# Rail_1.net
KiCad netlist of a schematic drawn in Altium Designer
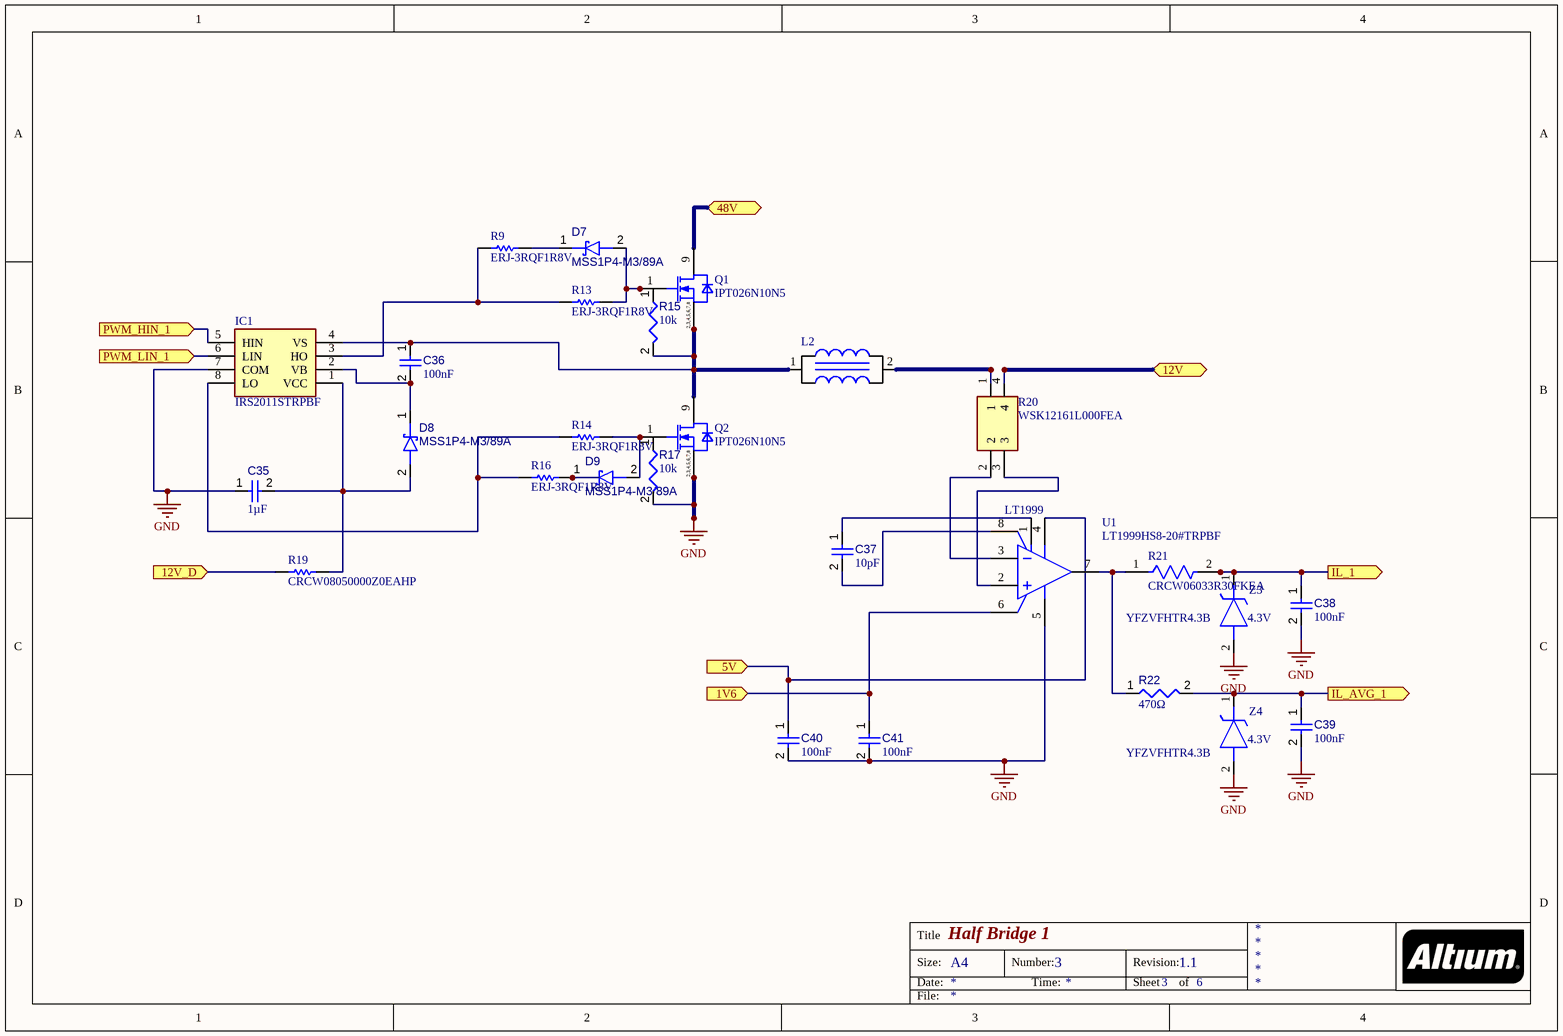
[diagram p0: Rail_1.SchDoc]

(export (version "E")
  (design (tool "Eeschema 10.0.6"))
  (components
    (comp (ref "C35")
      (value "1µF")
      (footprint "CAPC0603(1608)100_L")
      (description "Chip Capacitor, 1µF +/-0.1%, 25V, 0603, Thickness 1 mm")
      (fields (field (name "TOLERANCE") "20%") (field (name "Comment") "Capacitor 1µF +/-0.1% 25V 0603"))
      (libsource (lib "University of Paderborn") (part "CAP-NP-2"))
    )
    (comp (ref "C36")
      (value "100nF")
      (footprint "CAPC1608X90X40ML10T20")
      (description "Chip Capacitor, 100 nF, +/- 10%, 50 V, 0603 (1608 Metric)")
      (fields (field (name "TOLERANCE") "10%") (field (name "Comment") "Capacitor 100 nF +/-10% 50 V 0603"))
      (libsource (lib "University of Paderborn") (part "CAP-NP-2"))
    )
    (comp (ref "C37")
      (value "10pF")
      (footprint "CAPC1608X87X35ML15T15")
      (description "Chip Capacitor, 10 pF, +/- 0.25 pF, 50 V, 0603 (1608 Metric)")
      (fields
        (field (name "TOLERANCE") "0.25%")
        (field (name "Comment") "Capacitor 10 pF +/- 0.25 pF 50 V 0603")
      )
      (libsource (lib "University of Paderborn") (part "CAP-NP-2"))
    )
    (comp (ref "C38")
      (value "100nF")
      (footprint "CAPC1608X90X40ML10T20")
      (description "Chip Capacitor, 100 nF, +/- 10%, 50 V, 0603 (1608 Metric)")
      (fields (field (name "TOLERANCE") "10%") (field (name "Comment") "Capacitor 100 nF +/-10% 50 V 0603"))
      (libsource (lib "University of Paderborn") (part "CAP-NP-2"))
    )
    (comp (ref "C39")
      (value "100nF")
      (footprint "CAPC1608X90X40ML10T20")
      (description "Chip Capacitor, 100 nF, +/- 10%, 50 V, 0603 (1608 Metric)")
      (fields (field (name "TOLERANCE") "10%") (field (name "Comment") "Capacitor 100 nF +/-10% 50 V 0603"))
      (libsource (lib "University of Paderborn") (part "CAP-NP-2"))
    )
    (comp (ref "C40")
      (value "100nF")
      (footprint "CAPC1608X90X40ML10T20")
      (description "Chip Capacitor, 100 nF, +/- 10%, 50 V, 0603 (1608 Metric)")
      (fields (field (name "TOLERANCE") "10%") (field (name "Comment") "Capacitor 100 nF +/-10% 50 V 0603"))
      (libsource (lib "University of Paderborn") (part "CAP-NP-2"))
    )
    (comp (ref "C41")
      (value "100nF")
      (footprint "CAPC1608X90X40ML10T20")
      (description "Chip Capacitor, 100 nF, +/- 10%, 50 V, 0603 (1608 Metric)")
      (fields (field (name "TOLERANCE") "10%") (field (name "Comment") "Capacitor 100 nF +/-10% 50 V 0603"))
      (libsource (lib "University of Paderborn") (part "CAP-NP-2"))
    )
    (comp (ref "D7")
      (value "MSS1P4-M3/89A")
      (footprint "MicroSMP (DO-219AD)")
      (description "Schottky Diodes & Rectifiers 1.0 Amp 40 Volt")
      (libsource (lib "University of Paderborn") (part "D-SKY-KA2"))
    )
    (comp (ref "D8")
      (value "MSS1P4-M3/89A")
      (footprint "MicroSMP (DO-219AD)")
      (description "Schottky Diodes & Rectifiers 1.0 Amp 40 Volt")
      (libsource (lib "University of Paderborn") (part "D-SKY-KA2"))
    )
    (comp (ref "D9")
      (value "MSS1P4-M3/89A")
      (footprint "MicroSMP (DO-219AD)")
      (description "Schottky Diodes & Rectifiers 1.0 Amp 40 Volt")
      (libsource (lib "University of Paderborn") (part "D-SKY-KA2"))
    )
    (comp (ref "IC1")
      (value "IRS2011STRPBF")
      (footprint "SOIC127P600X175-8N-12-V")
      (description "Integrated Circuit")
      (fields (field (name "MOUSER PART NUMBER") "942-IRS2011STRPBF"))
      (libsource (lib "*") (part "IRS2011STRPBF"))
    )
    (comp (ref "L2")
      (value "Inductor (Ansys)")
      (footprint "Inductor-Footprint-1")
      (description "Ansys 3D Model")
      (libsource (lib "University of Paderborn") (part "Inductor"))
    )
    (comp (ref "Q1")
      (value "IPT026N10N5")
      (footprint "INF-PG-HSOF-8-1-0-V")
      (fields (field (name "MANUFACTURER") "Infineon Technologies"))
      (libsource (lib "IPT026N10N5") (part "IPT026N10N5"))
    )
    (comp (ref "Q2")
      (value "IPT026N10N5")
      (footprint "INF-PG-HSOF-8-1-0-V")
      (fields (field (name "MANUFACTURER") "Infineon Technologies"))
      (libsource (lib "IPT026N10N5") (part "IPT026N10N5"))
    )
    (comp (ref "R9")
      (value "ERJ-3RQF1R8V")
      (footprint "RESC1608X55X30LL15T15")
      (fields (field (name "MANUFACTURER") "Panasonic"))
      (libsource (lib "Altium Content Vault") (part "RES"))
    )
    (comp (ref "R13")
      (value "ERJ-3RQF1R8V")
      (footprint "RESC1608X55X30LL15T15")
      (fields (field (name "MANUFACTURER") "Panasonic"))
      (libsource (lib "Altium Content Vault") (part "RES"))
    )
    (comp (ref "R14")
      (value "ERJ-3RQF1R8V")
      (footprint "RESC1608X55X30LL15T15")
      (fields (field (name "MANUFACTURER") "Panasonic"))
      (libsource (lib "Altium Content Vault") (part "RES"))
    )
    (comp (ref "R15")
      (value "10k")
      (footprint "RESC1608X55X25ML10T15")
      (description "Chip Resistor, 10 KOhm, +/- 1%, 01 W, -55 to 155 degC, 0603 (1608 Metric)")
      (fields (field (name "TOLERANCE") "1%") (field (name "POWER") "100mW"))
      (libsource (lib "University of Paderborn") (part "RES-2"))
    )
    (comp (ref "R16")
      (value "ERJ-3RQF1R8V")
      (footprint "RESC1608X55X30LL15T15")
      (fields (field (name "MANUFACTURER") "Panasonic"))
      (libsource (lib "Altium Content Vault") (part "RES"))
    )
    (comp (ref "R17")
      (value "10k")
      (footprint "RESC1608X55X25ML10T15")
      (description "Chip Resistor, 10 KOhm, +/- 1%, 01 W, -55 to 155 degC, 0603 (1608 Metric)")
      (fields (field (name "TOLERANCE") "1%") (field (name "POWER") "100mW"))
      (libsource (lib "University of Paderborn") (part "RES-2"))
    )
    (comp (ref "R19")
      (value "CRCW08050000Z0EAHP")
      (footprint "RESC2013X50X30ML20T20")
      (fields (field (name "MANUFACTURER") "Vishay Dale"))
      (libsource (lib "Altium Content Vault") (part "RES"))
    )
    (comp (ref "R20")
      (value "WSK12161L000FEA")
      (footprint "SamacSys:WSK12161L000FEA")
      (description "Resistor")
      (fields (field (name "MOUSER PART NUMBER") "71-WSK12161L000FEA"))
      (libsource (lib "*") (part "WSK12161L000FEA"))
    )
    (comp (ref "R21")
      (value "CRCW06033R30FKEA")
      (footprint "FP-CRCW0603-e3-IPC_C")
      (description "RES Thick Film, 3.3Ω, 1%, 0.1W, 100ppm/°C, 0603")
      (fields (field (name "TOLERANCE") "1%"))
      (libsource (lib "Altium Content Vault") (part "1029c3af85768c4190bb7ad29bc67b5"))
    )
    (comp (ref "R22")
      (value "470Ω")
      (footprint "RESC0805(2012)_L")
      (description "470R 0.125W 5% 0805 (2012 Metric)  SMD")
      (fields (field (name "POWER") "0.125W") (field (name "TOLERANCE") "5%"))
      (libsource (lib "University of Paderborn") (part "470R5J"))
    )
    (comp (ref "U1")
      (value "LT1999HS8-20#TRPBF")
      (footprint "LT-S8-8_L")
      (fields
        (field (name "LINEAR TECHNOLOGY PART NUMBER") "LT1999-20")
        (field (name "MANUFACTURER") "Linear Technology")
      )
      (libsource (lib "Altium Content Vault") (part "LT-LT1999-8"))
    )
    (comp (ref "Z3")
      (value "YFZVFHTR4.3B")
      (footprint "SamacSys:YFZVFHTR43B")
      (description "Zener Diode")
      (fields (field (name "MOUSER PART NUMBER") "755-YFZVFHTR4.3B"))
      (libsource (lib "*") (part "YFZVFHTR4.3B"))
    )
    (comp (ref "Z4")
      (value "YFZVFHTR4.3B")
      (footprint "SamacSys:YFZVFHTR43B")
      (description "Zener Diode")
      (fields (field (name "MOUSER PART NUMBER") "755-YFZVFHTR4.3B"))
      (libsource (lib "*") (part "YFZVFHTR4.3B"))
    )
  )
  (nets
    (net (code "1") (name "/1V6") (class "Default")
      (node (ref "C41") (pin "1") (pinfunction "1_1") (pintype "passive"))
      (node (ref "U1") (pin "6") (pinfunction "REF_6") (pintype "passive"))
    )
    (net (code "2") (name "/5V") (class "Default")
      (node (ref "C40") (pin "1") (pinfunction "1_1") (pintype "passive"))
      (node (ref "U1") (pin "4") (pinfunction "V+_4") (pintype "passive"))
    )
    (net (code "3") (name "/12V") (class "Default")
      (node (ref "R20") (pin "4") (pinfunction "4_4") (pintype "passive"))
    )
    (net (code "4") (name "/12V_D") (class "Default")
      (node (ref "R19") (pin "1") (pinfunction "1_1") (pintype "passive"))
    )
    (net (code "5") (name "/48V") (class "Default")
      (node (ref "Q1") (pin "9") (pinfunction "DRAIN_9") (pintype "passive"))
    )
    (net (code "6") (name "/IL_1") (class "Default")
      (node (ref "C38") (pin "1") (pinfunction "1_1") (pintype "passive"))
      (node (ref "R21") (pin "2") (pinfunction "2_2") (pintype "passive"))
      (node (ref "Z3") (pin "1") (pinfunction "K_1") (pintype "passive"))
    )
    (net (code "7") (name "/IL_AVG_1") (class "Default")
      (node (ref "C39") (pin "1") (pinfunction "1_1") (pintype "passive"))
      (node (ref "R22") (pin "2") (pinfunction "2_2") (pintype "passive"))
      (node (ref "Z4") (pin "1") (pinfunction "K_1") (pintype "passive"))
    )
    (net (code "8") (name "/PWM_HIN_1") (class "Default")
      (node (ref "IC1") (pin "5") (pinfunction "HIN_5") (pintype "passive"))
    )
    (net (code "9") (name "/PWM_LIN_1") (class "Default")
      (node (ref "IC1") (pin "6") (pinfunction "LIN_6") (pintype "passive"))
    )
    (net (code "10") (name "GND") (class "Default")
      (node (ref "C35") (pin "1") (pinfunction "1_1") (pintype "passive"))
      (node (ref "C38") (pin "2") (pinfunction "2_2") (pintype "passive"))
      (node (ref "C39") (pin "2") (pinfunction "2_2") (pintype "passive"))
      (node (ref "C40") (pin "2") (pinfunction "2_2") (pintype "passive"))
      (node (ref "C41") (pin "2") (pinfunction "2_2") (pintype "passive"))
      (node (ref "IC1") (pin "7") (pinfunction "COM_7") (pintype "passive"))
      (node (ref "Q2") (pin "2") (pinfunction "SOURCE_2") (pintype "passive"))
      (node (ref "Q2") (pin "3") (pinfunction "SOURCE_3") (pintype "passive"))
      (node (ref "Q2") (pin "4") (pinfunction "SOURCE_4") (pintype "passive"))
      (node (ref "Q2") (pin "5") (pinfunction "SOURCE_5") (pintype "passive"))
      (node (ref "Q2") (pin "6") (pinfunction "SOURCE_6") (pintype "passive"))
      (node (ref "Q2") (pin "7") (pinfunction "SOURCE_7") (pintype "passive"))
      (node (ref "Q2") (pin "8") (pinfunction "SOURCE_8") (pintype "passive"))
      (node (ref "R17") (pin "2") (pinfunction "2_2") (pintype "passive"))
      (node (ref "U1") (pin "5") (pinfunction "GND_5") (pintype "passive"))
      (node (ref "Z3") (pin "2") (pinfunction "A_2") (pintype "passive"))
      (node (ref "Z4") (pin "2") (pinfunction "A_2") (pintype "passive"))
    )
    (net (code "11") (name "Net-(C37-Pad1)") (class "Default")
      (node (ref "C37") (pin "1") (pinfunction "1_1") (pintype "passive"))
      (node (ref "U1") (pin "1") (pinfunction "V+_1") (pintype "passive"))
    )
    (net (code "12") (name "Net-(D7-A)") (class "Default")
      (node (ref "D7") (pin "2") (pinfunction "A_2") (pintype "passive"))
      (node (ref "Q1") (pin "1") (pinfunction "GATE_1") (pintype "passive"))
      (node (ref "R13") (pin "2") (pinfunction "2_2") (pintype "passive"))
      (node (ref "R15") (pin "1") (pinfunction "1_1") (pintype "passive"))
    )
    (net (code "13") (name "Net-(D7-K)") (class "Default")
      (node (ref "D7") (pin "1") (pinfunction "K_1") (pintype "passive"))
      (node (ref "R9") (pin "2") (pinfunction "2_2") (pintype "passive"))
    )
    (net (code "14") (name "Net-(D8-A)") (class "Default")
      (node (ref "C35") (pin "2") (pinfunction "2_2") (pintype "passive"))
      (node (ref "D8") (pin "2") (pinfunction "A_2") (pintype "passive"))
      (node (ref "IC1") (pin "1") (pinfunction "VCC_1") (pintype "passive"))
      (node (ref "R19") (pin "2") (pinfunction "2_2") (pintype "passive"))
    )
    (net (code "15") (name "Net-(D8-K)") (class "Default")
      (node (ref "C36") (pin "2") (pinfunction "2_2") (pintype "passive"))
      (node (ref "D8") (pin "1") (pinfunction "K_1") (pintype "passive"))
      (node (ref "IC1") (pin "2") (pinfunction "VB_2") (pintype "passive"))
    )
    (net (code "16") (name "Net-(D9-A)") (class "Default")
      (node (ref "D9") (pin "2") (pinfunction "A_2") (pintype "passive"))
      (node (ref "Q2") (pin "1") (pinfunction "GATE_1") (pintype "passive"))
      (node (ref "R14") (pin "2") (pinfunction "2_2") (pintype "passive"))
      (node (ref "R17") (pin "1") (pinfunction "1_1") (pintype "passive"))
    )
    (net (code "17") (name "Net-(D9-K)") (class "Default")
      (node (ref "D9") (pin "1") (pinfunction "K_1") (pintype "passive"))
      (node (ref "R16") (pin "2") (pinfunction "2_2") (pintype "passive"))
    )
    (net (code "18") (name "Net-(IC1-HO)") (class "Default")
      (node (ref "IC1") (pin "3") (pinfunction "HO_3") (pintype "passive"))
      (node (ref "R13") (pin "1") (pinfunction "1_1") (pintype "passive"))
      (node (ref "R9") (pin "1") (pinfunction "1_1") (pintype "passive"))
    )
    (net (code "19") (name "Net-(IC1-LO)") (class "Default")
      (node (ref "IC1") (pin "8") (pinfunction "LO_8") (pintype "passive"))
      (node (ref "R14") (pin "1") (pinfunction "1_1") (pintype "passive"))
      (node (ref "R16") (pin "1") (pinfunction "1_1") (pintype "passive"))
    )
    (net (code "20") (name "Net-(IC1-VS)") (class "Default")
      (node (ref "C36") (pin "1") (pinfunction "1_1") (pintype "passive"))
      (node (ref "IC1") (pin "4") (pinfunction "VS_4") (pintype "passive"))
      (node (ref "L2") (pin "1") (pinfunction "1_1") (pintype "passive"))
      (node (ref "Q1") (pin "2") (pinfunction "SOURCE_2") (pintype "passive"))
      (node (ref "Q1") (pin "3") (pinfunction "SOURCE_3") (pintype "passive"))
      (node (ref "Q1") (pin "4") (pinfunction "SOURCE_4") (pintype "passive"))
      (node (ref "Q1") (pin "5") (pinfunction "SOURCE_5") (pintype "passive"))
      (node (ref "Q1") (pin "6") (pinfunction "SOURCE_6") (pintype "passive"))
      (node (ref "Q1") (pin "7") (pinfunction "SOURCE_7") (pintype "passive"))
      (node (ref "Q1") (pin "8") (pinfunction "SOURCE_8") (pintype "passive"))
      (node (ref "Q2") (pin "9") (pinfunction "DRAIN_9") (pintype "passive"))
      (node (ref "R15") (pin "2") (pinfunction "2_2") (pintype "passive"))
    )
    (net (code "21") (name "Net-(L2-Pad2)") (class "Default")
      (node (ref "L2") (pin "2") (pinfunction "2_2") (pintype "passive"))
      (node (ref "R20") (pin "1") (pinfunction "1_1") (pintype "passive"))
    )
    (net (code "22") (name "Net-(U1-+IN)") (class "Default")
      (node (ref "R20") (pin "3") (pinfunction "3_3") (pintype "passive"))
      (node (ref "U1") (pin "2") (pinfunction "+IN_2") (pintype "passive"))
    )
    (net (code "23") (name "Net-(U1--IN)") (class "Default")
      (node (ref "R20") (pin "2") (pinfunction "2_2") (pintype "passive"))
      (node (ref "U1") (pin "3") (pinfunction "-IN_3") (pintype "passive"))
    )
    (net (code "24") (name "Net-(U1-OUT)") (class "Default")
      (node (ref "R21") (pin "1") (pinfunction "1_1") (pintype "passive"))
      (node (ref "R22") (pin "1") (pinfunction "1_1") (pintype "passive"))
      (node (ref "U1") (pin "7") (pinfunction "OUT_7") (pintype "passive"))
    )
    (net (code "25") (name "Net-(U1-~{SHDN})") (class "Default")
      (node (ref "C37") (pin "2") (pinfunction "2_2") (pintype "passive"))
      (node (ref "U1") (pin "8") (pinfunction "~{SHDN}_8") (pintype "passive"))
    )
  )
)
